# ETHERNET.net
KiCad netlist of a schematic drawn in Altium Designer
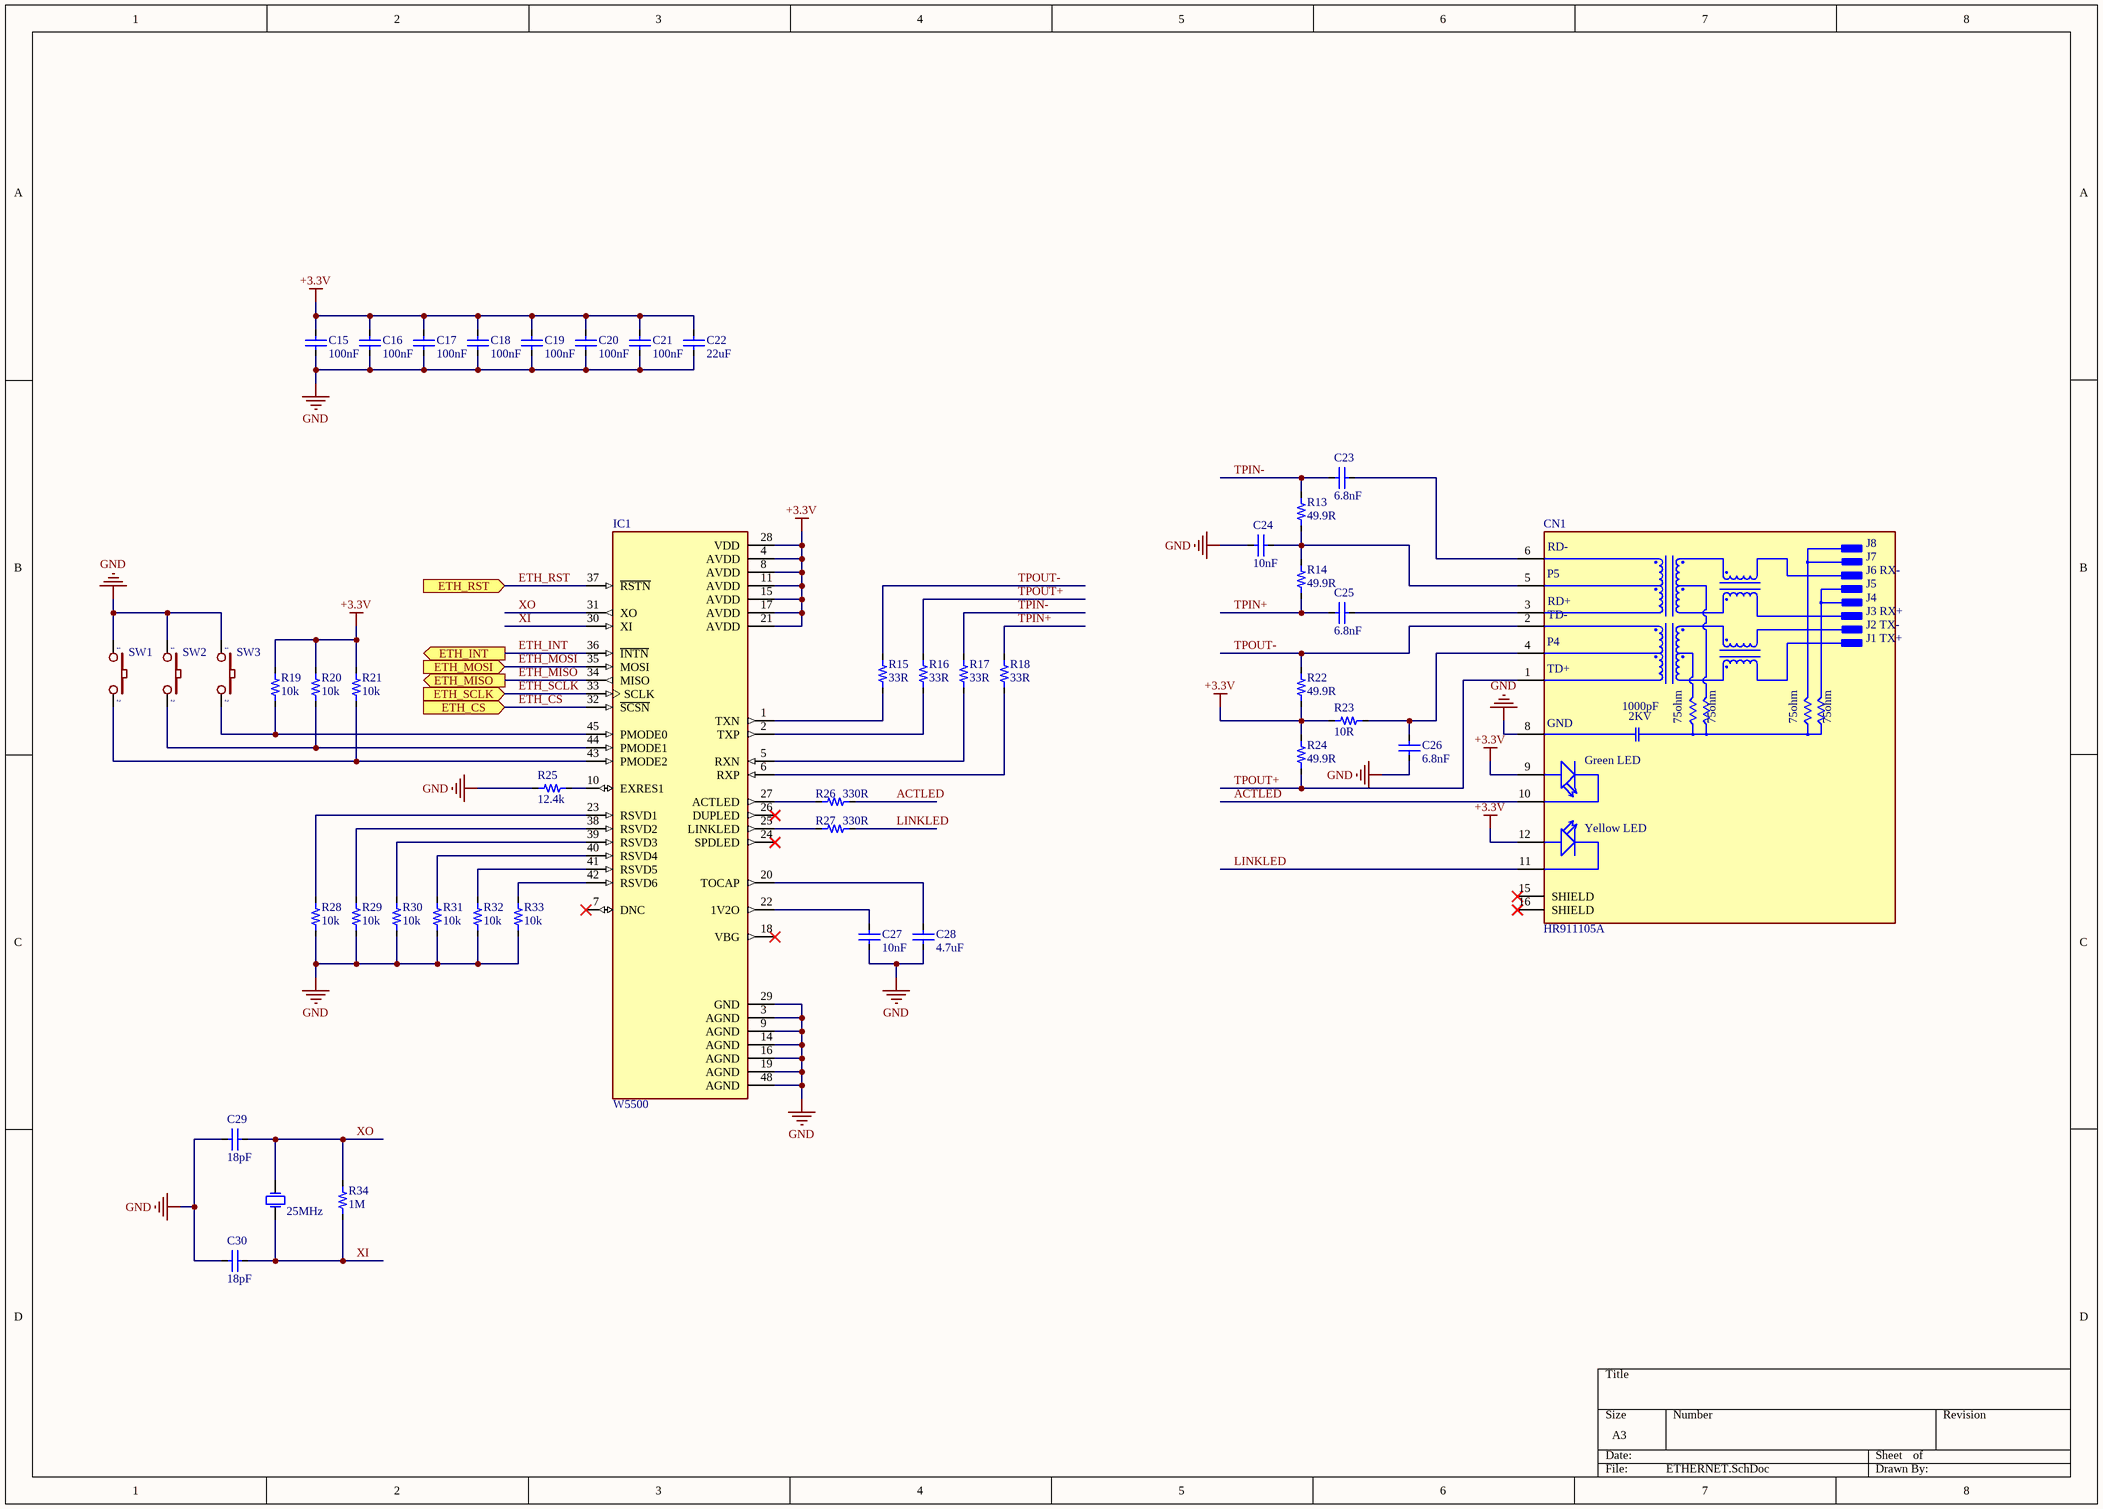
[diagram p0: ETHERNET.SchDoc]

(export (version "E")
  (design (tool "Eeschema 10.0.6"))
  (components
    (comp (ref "C15")
      (value "100nF")
      (footprint "CAP_0603")
      (description "Capacitor")
      (fields (field (name "PUBLISHER") "Altium Limited"))
      (libsource (lib "My Library") (part "CapSMD"))
    )
    (comp (ref "C16")
      (value "100nF")
      (footprint "CAP_0603")
      (description "Capacitor")
      (fields (field (name "PUBLISHER") "Altium Limited"))
      (libsource (lib "My Library") (part "CapSMD"))
    )
    (comp (ref "C17")
      (value "100nF")
      (footprint "CAP_0603")
      (description "Capacitor")
      (fields (field (name "PUBLISHER") "Altium Limited"))
      (libsource (lib "My Library") (part "CapSMD"))
    )
    (comp (ref "C18")
      (value "100nF")
      (footprint "CAP_0603")
      (description "Capacitor")
      (fields (field (name "PUBLISHER") "Altium Limited"))
      (libsource (lib "My Library") (part "CapSMD"))
    )
    (comp (ref "C19")
      (value "100nF")
      (footprint "CAP_0603")
      (description "Capacitor")
      (fields (field (name "PUBLISHER") "Altium Limited"))
      (libsource (lib "My Library") (part "CapSMD"))
    )
    (comp (ref "C20")
      (value "100nF")
      (footprint "CAP_0603")
      (description "Capacitor")
      (fields (field (name "PUBLISHER") "Altium Limited"))
      (libsource (lib "My Library") (part "CapSMD"))
    )
    (comp (ref "C21")
      (value "100nF")
      (footprint "CAP_0603")
      (description "Capacitor")
      (fields (field (name "PUBLISHER") "Altium Limited"))
      (libsource (lib "My Library") (part "CapSMD"))
    )
    (comp (ref "C22")
      (value "22uF")
      (footprint "CAP_0603")
      (description "Capacitor")
      (fields (field (name "PUBLISHER") "Altium Limited"))
      (libsource (lib "My Library") (part "CapSMD"))
    )
    (comp (ref "C23")
      (value "6.8nF")
      (footprint "CAP_0603")
      (description "Capacitor")
      (fields (field (name "PUBLISHER") "Altium Limited"))
      (libsource (lib "My Library") (part "CapSMD"))
    )
    (comp (ref "C24")
      (value "10nF")
      (footprint "CAP_0603")
      (description "Capacitor")
      (fields (field (name "PUBLISHER") "Altium Limited"))
      (libsource (lib "My Library") (part "CapSMD"))
    )
    (comp (ref "C25")
      (value "6.8nF")
      (footprint "CAP_0603")
      (description "Capacitor")
      (fields (field (name "PUBLISHER") "Altium Limited"))
      (libsource (lib "My Library") (part "CapSMD"))
    )
    (comp (ref "C26")
      (value "6.8nF")
      (footprint "CAP_0603")
      (description "Capacitor")
      (fields (field (name "PUBLISHER") "Altium Limited"))
      (libsource (lib "My Library") (part "CapSMD"))
    )
    (comp (ref "C27")
      (value "10nF")
      (footprint "CAP_0603")
      (description "Capacitor")
      (fields (field (name "PUBLISHER") "Altium Limited"))
      (libsource (lib "My Library") (part "CapSMD"))
    )
    (comp (ref "C28")
      (value "4.7uF")
      (footprint "CAP_0603")
      (description "Capacitor")
      (fields (field (name "PUBLISHER") "Altium Limited"))
      (libsource (lib "My Library") (part "CapSMD"))
    )
    (comp (ref "C29")
      (value "18pF")
      (footprint "CAP_0603")
      (description "Capacitor")
      (fields (field (name "PUBLISHER") "Altium Limited"))
      (libsource (lib "My Library") (part "CapSMD"))
    )
    (comp (ref "C30")
      (value "18pF")
      (footprint "CAP_0603")
      (description "Capacitor")
      (fields (field (name "PUBLISHER") "Altium Limited"))
      (libsource (lib "My Library") (part "CapSMD"))
    )
    (comp (ref "CN1")
      (value "HR911105A")
      (footprint "HR911105A")
      (libsource (lib "Dung Library") (part "HR911105A"))
    )
    (comp (ref "IC1") (value "W5500") (footprint "W5500") (libsource (lib "Dung Library") (part "W5500")))
    (comp (ref "R13")
      (value "49.9R")
      (footprint "RES-SMD-0603")
      (description "Resistor")
      (fields
        (field (name "MANUFACTURER") "Generic Components")
        (field (name "PUBLISHER") "Altium Hobart Technology Centre")
      )
      (libsource (lib "My Library") (part "Resistor - SMD"))
    )
    (comp (ref "R14")
      (value "49.9R")
      (footprint "RES-SMD-0603")
      (description "Resistor")
      (fields
        (field (name "MANUFACTURER") "Generic Components")
        (field (name "PUBLISHER") "Altium Hobart Technology Centre")
      )
      (libsource (lib "My Library") (part "Resistor - SMD"))
    )
    (comp (ref "R15")
      (value "33R")
      (footprint "RES-SMD-0603")
      (description "Resistor")
      (fields
        (field (name "MANUFACTURER") "Generic Components")
        (field (name "PUBLISHER") "Altium Hobart Technology Centre")
      )
      (libsource (lib "My Library") (part "Resistor - SMD"))
    )
    (comp (ref "R16")
      (value "33R")
      (footprint "RES-SMD-0603")
      (description "Resistor")
      (fields
        (field (name "MANUFACTURER") "Generic Components")
        (field (name "PUBLISHER") "Altium Hobart Technology Centre")
      )
      (libsource (lib "My Library") (part "Resistor - SMD"))
    )
    (comp (ref "R17")
      (value "33R")
      (footprint "RES-SMD-0603")
      (description "Resistor")
      (fields
        (field (name "MANUFACTURER") "Generic Components")
        (field (name "PUBLISHER") "Altium Hobart Technology Centre")
      )
      (libsource (lib "My Library") (part "Resistor - SMD"))
    )
    (comp (ref "R18")
      (value "33R")
      (footprint "RES-SMD-0603")
      (description "Resistor")
      (fields
        (field (name "MANUFACTURER") "Generic Components")
        (field (name "PUBLISHER") "Altium Hobart Technology Centre")
      )
      (libsource (lib "My Library") (part "Resistor - SMD"))
    )
    (comp (ref "R19")
      (value "10k")
      (footprint "RES-SMD-0603")
      (description "Resistor")
      (fields
        (field (name "MANUFACTURER") "Generic Components")
        (field (name "PUBLISHER") "Altium Hobart Technology Centre")
      )
      (libsource (lib "My Library") (part "Resistor - SMD"))
    )
    (comp (ref "R20")
      (value "10k")
      (footprint "RES-SMD-0603")
      (description "Resistor")
      (fields
        (field (name "MANUFACTURER") "Generic Components")
        (field (name "PUBLISHER") "Altium Hobart Technology Centre")
      )
      (libsource (lib "My Library") (part "Resistor - SMD"))
    )
    (comp (ref "R21")
      (value "10k")
      (footprint "RES-SMD-0603")
      (description "Resistor")
      (fields
        (field (name "MANUFACTURER") "Generic Components")
        (field (name "PUBLISHER") "Altium Hobart Technology Centre")
      )
      (libsource (lib "My Library") (part "Resistor - SMD"))
    )
    (comp (ref "R22")
      (value "49.9R")
      (footprint "RES-SMD-0603")
      (description "Resistor")
      (fields
        (field (name "MANUFACTURER") "Generic Components")
        (field (name "PUBLISHER") "Altium Hobart Technology Centre")
      )
      (libsource (lib "My Library") (part "Resistor - SMD"))
    )
    (comp (ref "R23")
      (value "10R")
      (footprint "RES-SMD-0603")
      (description "Resistor")
      (fields
        (field (name "MANUFACTURER") "Generic Components")
        (field (name "PUBLISHER") "Altium Hobart Technology Centre")
      )
      (libsource (lib "My Library") (part "Resistor - SMD"))
    )
    (comp (ref "R24")
      (value "49.9R")
      (footprint "RES-SMD-0603")
      (description "Resistor")
      (fields
        (field (name "MANUFACTURER") "Generic Components")
        (field (name "PUBLISHER") "Altium Hobart Technology Centre")
      )
      (libsource (lib "My Library") (part "Resistor - SMD"))
    )
    (comp (ref "R25")
      (value "12.4k")
      (footprint "RES-SMD-0603")
      (description "Resistor")
      (fields
        (field (name "MANUFACTURER") "Generic Components")
        (field (name "PUBLISHER") "Altium Hobart Technology Centre")
      )
      (libsource (lib "My Library") (part "Resistor - SMD"))
    )
    (comp (ref "R26")
      (value "330R")
      (footprint "RES-SMD-0603")
      (description "Resistor")
      (fields
        (field (name "MANUFACTURER") "Generic Components")
        (field (name "PUBLISHER") "Altium Hobart Technology Centre")
      )
      (libsource (lib "My Library") (part "Resistor - SMD"))
    )
    (comp (ref "R27")
      (value "330R")
      (footprint "RES-SMD-0603")
      (description "Resistor")
      (fields
        (field (name "MANUFACTURER") "Generic Components")
        (field (name "PUBLISHER") "Altium Hobart Technology Centre")
      )
      (libsource (lib "My Library") (part "Resistor - SMD"))
    )
    (comp (ref "R28")
      (value "10k")
      (footprint "RES-SMD-0603")
      (description "Resistor")
      (fields
        (field (name "MANUFACTURER") "Generic Components")
        (field (name "PUBLISHER") "Altium Hobart Technology Centre")
      )
      (libsource (lib "My Library") (part "Resistor - SMD"))
    )
    (comp (ref "R29")
      (value "10k")
      (footprint "RES-SMD-0603")
      (description "Resistor")
      (fields
        (field (name "MANUFACTURER") "Generic Components")
        (field (name "PUBLISHER") "Altium Hobart Technology Centre")
      )
      (libsource (lib "My Library") (part "Resistor - SMD"))
    )
    (comp (ref "R30")
      (value "10k")
      (footprint "RES-SMD-0603")
      (description "Resistor")
      (fields
        (field (name "MANUFACTURER") "Generic Components")
        (field (name "PUBLISHER") "Altium Hobart Technology Centre")
      )
      (libsource (lib "My Library") (part "Resistor - SMD"))
    )
    (comp (ref "R31")
      (value "10k")
      (footprint "RES-SMD-0603")
      (description "Resistor")
      (fields
        (field (name "MANUFACTURER") "Generic Components")
        (field (name "PUBLISHER") "Altium Hobart Technology Centre")
      )
      (libsource (lib "My Library") (part "Resistor - SMD"))
    )
    (comp (ref "R32")
      (value "10k")
      (footprint "RES-SMD-0603")
      (description "Resistor")
      (fields
        (field (name "MANUFACTURER") "Generic Components")
        (field (name "PUBLISHER") "Altium Hobart Technology Centre")
      )
      (libsource (lib "My Library") (part "Resistor - SMD"))
    )
    (comp (ref "R33")
      (value "10k")
      (footprint "RES-SMD-0603")
      (description "Resistor")
      (fields
        (field (name "MANUFACTURER") "Generic Components")
        (field (name "PUBLISHER") "Altium Hobart Technology Centre")
      )
      (libsource (lib "My Library") (part "Resistor - SMD"))
    )
    (comp (ref "R34")
      (value "1M")
      (footprint "RES-SMD-0603")
      (description "Resistor")
      (fields
        (field (name "MANUFACTURER") "Generic Components")
        (field (name "PUBLISHER") "Altium Hobart Technology Centre")
      )
      (libsource (lib "My Library") (part "Resistor - SMD"))
    )
    (comp (ref "SW1") (value "SW") (footprint "SW") (libsource (lib "Dung Library") (part "SW")))
    (comp (ref "SW2") (value "SW") (footprint "SW") (libsource (lib "Dung Library") (part "SW")))
    (comp (ref "SW3") (value "SW") (footprint "SW") (libsource (lib "Dung Library") (part "SW")))
    (comp (ref "Y1")
      (value "25MHz")
      (footprint "XTAL")
      (description "Crystal Oscillator")
      (fields (field (name "PUBLISHER") "Altium Limited"))
      (libsource (lib "Dung Library") (part "XTAL"))
    )
  )
  (nets
    (net (code "1") (name "+3.3V") (class "Default")
      (node (ref "C15") (pin "1") (pinfunction "1_1") (pintype "passive"))
      (node (ref "C16") (pin "1") (pinfunction "1_1") (pintype "passive"))
      (node (ref "C17") (pin "1") (pinfunction "1_1") (pintype "passive"))
      (node (ref "C18") (pin "1") (pinfunction "1_1") (pintype "passive"))
      (node (ref "C19") (pin "1") (pinfunction "1_1") (pintype "passive"))
      (node (ref "C20") (pin "1") (pinfunction "1_1") (pintype "passive"))
      (node (ref "C21") (pin "1") (pinfunction "1_1") (pintype "passive"))
      (node (ref "C22") (pin "1") (pinfunction "1_1") (pintype "passive"))
      (node (ref "CN1") (pin "12") (pinfunction "YA_12") (pintype "passive"))
      (node (ref "CN1") (pin "9") (pinfunction "GA_9") (pintype "passive"))
      (node (ref "IC1") (pin "11") (pinfunction "AVDD_11") (pintype "power_in"))
      (node (ref "IC1") (pin "15") (pinfunction "AVDD_15") (pintype "power_in"))
      (node (ref "IC1") (pin "17") (pinfunction "AVDD_17") (pintype "power_in"))
      (node (ref "IC1") (pin "21") (pinfunction "AVDD_21") (pintype "power_in"))
      (node (ref "IC1") (pin "28") (pinfunction "VDD_28") (pintype "power_in"))
      (node (ref "IC1") (pin "4") (pinfunction "AVDD_4") (pintype "power_in"))
      (node (ref "IC1") (pin "8") (pinfunction "AVDD_8") (pintype "power_in"))
      (node (ref "R19") (pin "2") (pinfunction "2_2") (pintype "passive"))
      (node (ref "R20") (pin "2") (pinfunction "2_2") (pintype "passive"))
      (node (ref "R21") (pin "2") (pinfunction "2_2") (pintype "passive"))
      (node (ref "R22") (pin "2") (pinfunction "2_2") (pintype "passive"))
      (node (ref "R23") (pin "1") (pinfunction "1_1") (pintype "passive"))
      (node (ref "R24") (pin "1") (pinfunction "1_1") (pintype "passive"))
    )
    (net (code "2") (name "/ACTLED") (class "Default")
      (node (ref "CN1") (pin "10") (pinfunction "GC_10") (pintype "passive"))
      (node (ref "R26") (pin "2") (pinfunction "2_2") (pintype "passive"))
    )
    (net (code "3") (name "/ETH_CS") (class "Default")
      (node (ref "IC1") (pin "32") (pinfunction "~{SCSN}_32") (pintype "input"))
    )
    (net (code "4") (name "/ETH_INT") (class "Default")
      (node (ref "IC1") (pin "36") (pinfunction "~{INTN}_36") (pintype "input"))
    )
    (net (code "5") (name "/ETH_MISO") (class "Default")
      (node (ref "IC1") (pin "34") (pinfunction "MISO_34") (pintype "output"))
    )
    (net (code "6") (name "/ETH_MOSI") (class "Default")
      (node (ref "IC1") (pin "35") (pinfunction "MOSI_35") (pintype "input"))
    )
    (net (code "7") (name "/ETH_RST") (class "Default")
      (node (ref "IC1") (pin "37") (pinfunction "~{RSTN}_37") (pintype "input"))
    )
    (net (code "8") (name "/ETH_SCLK") (class "Default")
      (node (ref "IC1") (pin "33") (pinfunction "SCLK_33") (pintype "input"))
    )
    (net (code "9") (name "/LINKLED") (class "Default")
      (node (ref "CN1") (pin "11") (pinfunction "YC_11") (pintype "passive"))
      (node (ref "R27") (pin "2") (pinfunction "2_2") (pintype "passive"))
    )
    (net (code "10") (name "/TPIN+") (class "Default")
      (node (ref "C25") (pin "2") (pinfunction "2_2") (pintype "passive"))
      (node (ref "R14") (pin "2") (pinfunction "2_2") (pintype "passive"))
      (node (ref "R18") (pin "1") (pinfunction "1_1") (pintype "passive"))
    )
    (net (code "11") (name "/TPIN-") (class "Default")
      (node (ref "C23") (pin "2") (pinfunction "2_2") (pintype "passive"))
      (node (ref "R13") (pin "1") (pinfunction "1_1") (pintype "passive"))
      (node (ref "R17") (pin "1") (pinfunction "1_1") (pintype "passive"))
    )
    (net (code "12") (name "/TPOUT+") (class "Default")
      (node (ref "CN1") (pin "1") (pinfunction "TD+_1") (pintype "passive"))
      (node (ref "R16") (pin "1") (pinfunction "1_1") (pintype "passive"))
      (node (ref "R24") (pin "2") (pinfunction "2_2") (pintype "passive"))
    )
    (net (code "13") (name "/TPOUT-") (class "Default")
      (node (ref "CN1") (pin "2") (pinfunction "TD-_2") (pintype "passive"))
      (node (ref "R15") (pin "1") (pinfunction "1_1") (pintype "passive"))
      (node (ref "R22") (pin "1") (pinfunction "1_1") (pintype "passive"))
    )
    (net (code "14") (name "/XI") (class "Default")
      (node (ref "C30") (pin "2") (pinfunction "2_2") (pintype "passive"))
      (node (ref "IC1") (pin "30") (pinfunction "XI_30") (pintype "input"))
      (node (ref "R34") (pin "1") (pinfunction "1_1") (pintype "passive"))
      (node (ref "Y1") (pin "2") (pinfunction "OSC2_2") (pintype "passive"))
    )
    (net (code "15") (name "/XO") (class "Default")
      (node (ref "C29") (pin "2") (pinfunction "2_2") (pintype "passive"))
      (node (ref "IC1") (pin "31") (pinfunction "XO_31") (pintype "output"))
      (node (ref "R34") (pin "2") (pinfunction "2_2") (pintype "passive"))
      (node (ref "Y1") (pin "1") (pinfunction "OSC1_1") (pintype "passive"))
    )
    (net (code "16") (name "GND") (class "Default")
      (node (ref "C15") (pin "2") (pinfunction "2_2") (pintype "passive"))
      (node (ref "C16") (pin "2") (pinfunction "2_2") (pintype "passive"))
      (node (ref "C17") (pin "2") (pinfunction "2_2") (pintype "passive"))
      (node (ref "C18") (pin "2") (pinfunction "2_2") (pintype "passive"))
      (node (ref "C19") (pin "2") (pinfunction "2_2") (pintype "passive"))
      (node (ref "C20") (pin "2") (pinfunction "2_2") (pintype "passive"))
      (node (ref "C21") (pin "2") (pinfunction "2_2") (pintype "passive"))
      (node (ref "C22") (pin "2") (pinfunction "2_2") (pintype "passive"))
      (node (ref "C24") (pin "2") (pinfunction "2_2") (pintype "passive"))
      (node (ref "C26") (pin "2") (pinfunction "2_2") (pintype "passive"))
      (node (ref "C27") (pin "1") (pinfunction "1_1") (pintype "passive"))
      (node (ref "C28") (pin "1") (pinfunction "1_1") (pintype "passive"))
      (node (ref "C29") (pin "1") (pinfunction "1_1") (pintype "passive"))
      (node (ref "C30") (pin "1") (pinfunction "1_1") (pintype "passive"))
      (node (ref "CN1") (pin "8") (pinfunction "GND_8") (pintype "power_in"))
      (node (ref "IC1") (pin "14") (pinfunction "AGND_14") (pintype "power_in"))
      (node (ref "IC1") (pin "16") (pinfunction "AGND_16") (pintype "power_in"))
      (node (ref "IC1") (pin "19") (pinfunction "AGND_19") (pintype "power_in"))
      (node (ref "IC1") (pin "29") (pinfunction "GND_29") (pintype "passive"))
      (node (ref "IC1") (pin "3") (pinfunction "AGND_3") (pintype "power_in"))
      (node (ref "IC1") (pin "48") (pinfunction "AGND_48") (pintype "power_in"))
      (node (ref "IC1") (pin "9") (pinfunction "AGND_9") (pintype "power_in"))
      (node (ref "R25") (pin "1") (pinfunction "1_1") (pintype "passive"))
      (node (ref "R28") (pin "1") (pinfunction "1_1") (pintype "passive"))
      (node (ref "R29") (pin "1") (pinfunction "1_1") (pintype "passive"))
      (node (ref "R30") (pin "1") (pinfunction "1_1") (pintype "passive"))
      (node (ref "R31") (pin "1") (pinfunction "1_1") (pintype "passive"))
      (node (ref "R32") (pin "1") (pinfunction "1_1") (pintype "passive"))
      (node (ref "R33") (pin "1") (pinfunction "1_1") (pintype "passive"))
      (node (ref "SW1") (pin "1") (pinfunction "1_1") (pintype "passive"))
      (node (ref "SW2") (pin "1") (pinfunction "1_1") (pintype "passive"))
      (node (ref "SW3") (pin "1") (pinfunction "1_1") (pintype "passive"))
    )
    (net (code "17") (name "Net-(CN1-P4)") (class "Default")
      (node (ref "C26") (pin "1") (pinfunction "1_1") (pintype "passive"))
      (node (ref "CN1") (pin "4") (pinfunction "P4_4") (pintype "passive"))
      (node (ref "R23") (pin "2") (pinfunction "2_2") (pintype "passive"))
    )
    (net (code "18") (name "Net-(CN1-P5)") (class "Default")
      (node (ref "C24") (pin "1") (pinfunction "1_1") (pintype "passive"))
      (node (ref "CN1") (pin "5") (pinfunction "P5_5") (pintype "passive"))
      (node (ref "R13") (pin "2") (pinfunction "2_2") (pintype "passive"))
      (node (ref "R14") (pin "1") (pinfunction "1_1") (pintype "passive"))
    )
    (net (code "19") (name "Net-(CN1-RD+)") (class "Default")
      (node (ref "C25") (pin "1") (pinfunction "1_1") (pintype "passive"))
      (node (ref "CN1") (pin "3") (pinfunction "RD+_3") (pintype "passive"))
    )
    (net (code "20") (name "Net-(CN1-RD-)") (class "Default")
      (node (ref "C23") (pin "1") (pinfunction "1_1") (pintype "passive"))
      (node (ref "CN1") (pin "6") (pinfunction "RD-_6") (pintype "passive"))
    )
    (net (code "21") (name "Net-(IC1-1V2O)") (class "Default")
      (node (ref "C27") (pin "2") (pinfunction "2_2") (pintype "passive"))
      (node (ref "IC1") (pin "22") (pinfunction "1V2O_22") (pintype "output"))
    )
    (net (code "22") (name "Net-(IC1-ACTLED)") (class "Default")
      (node (ref "IC1") (pin "27") (pinfunction "ACTLED_27") (pintype "output"))
      (node (ref "R26") (pin "1") (pinfunction "1_1") (pintype "passive"))
    )
    (net (code "23") (name "Net-(IC1-EXRES1)") (class "Default")
      (node (ref "IC1") (pin "10") (pinfunction "EXRES1_10") (pintype "bidirectional"))
      (node (ref "R25") (pin "2") (pinfunction "2_2") (pintype "passive"))
    )
    (net (code "24") (name "Net-(IC1-LINKLED)") (class "Default")
      (node (ref "IC1") (pin "25") (pinfunction "LINKLED_25") (pintype "output"))
      (node (ref "R27") (pin "1") (pinfunction "1_1") (pintype "passive"))
    )
    (net (code "25") (name "Net-(IC1-PMODE0)") (class "Default")
      (node (ref "IC1") (pin "45") (pinfunction "PMODE0_45") (pintype "input"))
      (node (ref "R19") (pin "1") (pinfunction "1_1") (pintype "passive"))
      (node (ref "SW3") (pin "2") (pinfunction "2_2") (pintype "passive"))
    )
    (net (code "26") (name "Net-(IC1-PMODE1)") (class "Default")
      (node (ref "IC1") (pin "44") (pinfunction "PMODE1_44") (pintype "input"))
      (node (ref "R20") (pin "1") (pinfunction "1_1") (pintype "passive"))
      (node (ref "SW2") (pin "2") (pinfunction "2_2") (pintype "passive"))
    )
    (net (code "27") (name "Net-(IC1-PMODE2)") (class "Default")
      (node (ref "IC1") (pin "43") (pinfunction "PMODE2_43") (pintype "input"))
      (node (ref "R21") (pin "1") (pinfunction "1_1") (pintype "passive"))
      (node (ref "SW1") (pin "2") (pinfunction "2_2") (pintype "passive"))
    )
    (net (code "28") (name "Net-(IC1-RSVD1)") (class "Default")
      (node (ref "IC1") (pin "23") (pinfunction "RSVD1_23") (pintype "input"))
      (node (ref "R28") (pin "2") (pinfunction "2_2") (pintype "passive"))
    )
    (net (code "29") (name "Net-(IC1-RSVD2)") (class "Default")
      (node (ref "IC1") (pin "38") (pinfunction "RSVD2_38") (pintype "input"))
      (node (ref "R29") (pin "2") (pinfunction "2_2") (pintype "passive"))
    )
    (net (code "30") (name "Net-(IC1-RSVD3)") (class "Default")
      (node (ref "IC1") (pin "39") (pinfunction "RSVD3_39") (pintype "input"))
      (node (ref "R30") (pin "2") (pinfunction "2_2") (pintype "passive"))
    )
    (net (code "31") (name "Net-(IC1-RSVD4)") (class "Default")
      (node (ref "IC1") (pin "40") (pinfunction "RSVD4_40") (pintype "input"))
      (node (ref "R31") (pin "2") (pinfunction "2_2") (pintype "passive"))
    )
    (net (code "32") (name "Net-(IC1-RSVD5)") (class "Default")
      (node (ref "IC1") (pin "41") (pinfunction "RSVD5_41") (pintype "input"))
      (node (ref "R32") (pin "2") (pinfunction "2_2") (pintype "passive"))
    )
    (net (code "33") (name "Net-(IC1-RSVD6)") (class "Default")
      (node (ref "IC1") (pin "42") (pinfunction "RSVD6_42") (pintype "input"))
      (node (ref "R33") (pin "2") (pinfunction "2_2") (pintype "passive"))
    )
    (net (code "34") (name "Net-(IC1-RXN)") (class "Default")
      (node (ref "IC1") (pin "5") (pinfunction "RXN_5") (pintype "input"))
      (node (ref "R17") (pin "2") (pinfunction "2_2") (pintype "passive"))
    )
    (net (code "35") (name "Net-(IC1-RXP)") (class "Default")
      (node (ref "IC1") (pin "6") (pinfunction "RXP_6") (pintype "input"))
      (node (ref "R18") (pin "2") (pinfunction "2_2") (pintype "passive"))
    )
    (net (code "36") (name "Net-(IC1-TOCAP)") (class "Default")
      (node (ref "C28") (pin "2") (pinfunction "2_2") (pintype "passive"))
      (node (ref "IC1") (pin "20") (pinfunction "TOCAP_20") (pintype "output"))
    )
    (net (code "37") (name "Net-(IC1-TXN)") (class "Default")
      (node (ref "IC1") (pin "1") (pinfunction "TXN_1") (pintype "output"))
      (node (ref "R15") (pin "2") (pinfunction "2_2") (pintype "passive"))
    )
    (net (code "38") (name "Net-(IC1-TXP)") (class "Default")
      (node (ref "IC1") (pin "2") (pinfunction "TXP_2") (pintype "output"))
      (node (ref "R16") (pin "2") (pinfunction "2_2") (pintype "passive"))
    )
    (net (code "39") (name "unconnected-(CN1-SHIELD-Pad15)") (class "Default")
      (node (ref "CN1") (pin "15") (pinfunction "SHIELD_15") (pintype "passive+no_connect"))
    )
    (net (code "40") (name "unconnected-(CN1-SHIELD-Pad16)") (class "Default")
      (node (ref "CN1") (pin "16") (pinfunction "SHIELD_16") (pintype "passive+no_connect"))
    )
    (net (code "41") (name "unconnected-(IC1-DNC-Pad7)") (class "Default")
      (node (ref "IC1") (pin "7") (pinfunction "DNC_7") (pintype "bidirectional+no_connect"))
    )
    (net (code "42") (name "unconnected-(IC1-DUPLED-Pad26)") (class "Default")
      (node (ref "IC1") (pin "26") (pinfunction "DUPLED_26") (pintype "output+no_connect"))
    )
    (net (code "43") (name "unconnected-(IC1-SPDLED-Pad24)") (class "Default")
      (node (ref "IC1") (pin "24") (pinfunction "SPDLED_24") (pintype "output+no_connect"))
    )
    (net (code "44") (name "unconnected-(IC1-VBG-Pad18)") (class "Default")
      (node (ref "IC1") (pin "18") (pinfunction "VBG_18") (pintype "output+no_connect"))
    )
  )
)
